# Heart_Rate_Monitoring_System.net
KiCad netlist of a schematic drawn in EAGLE
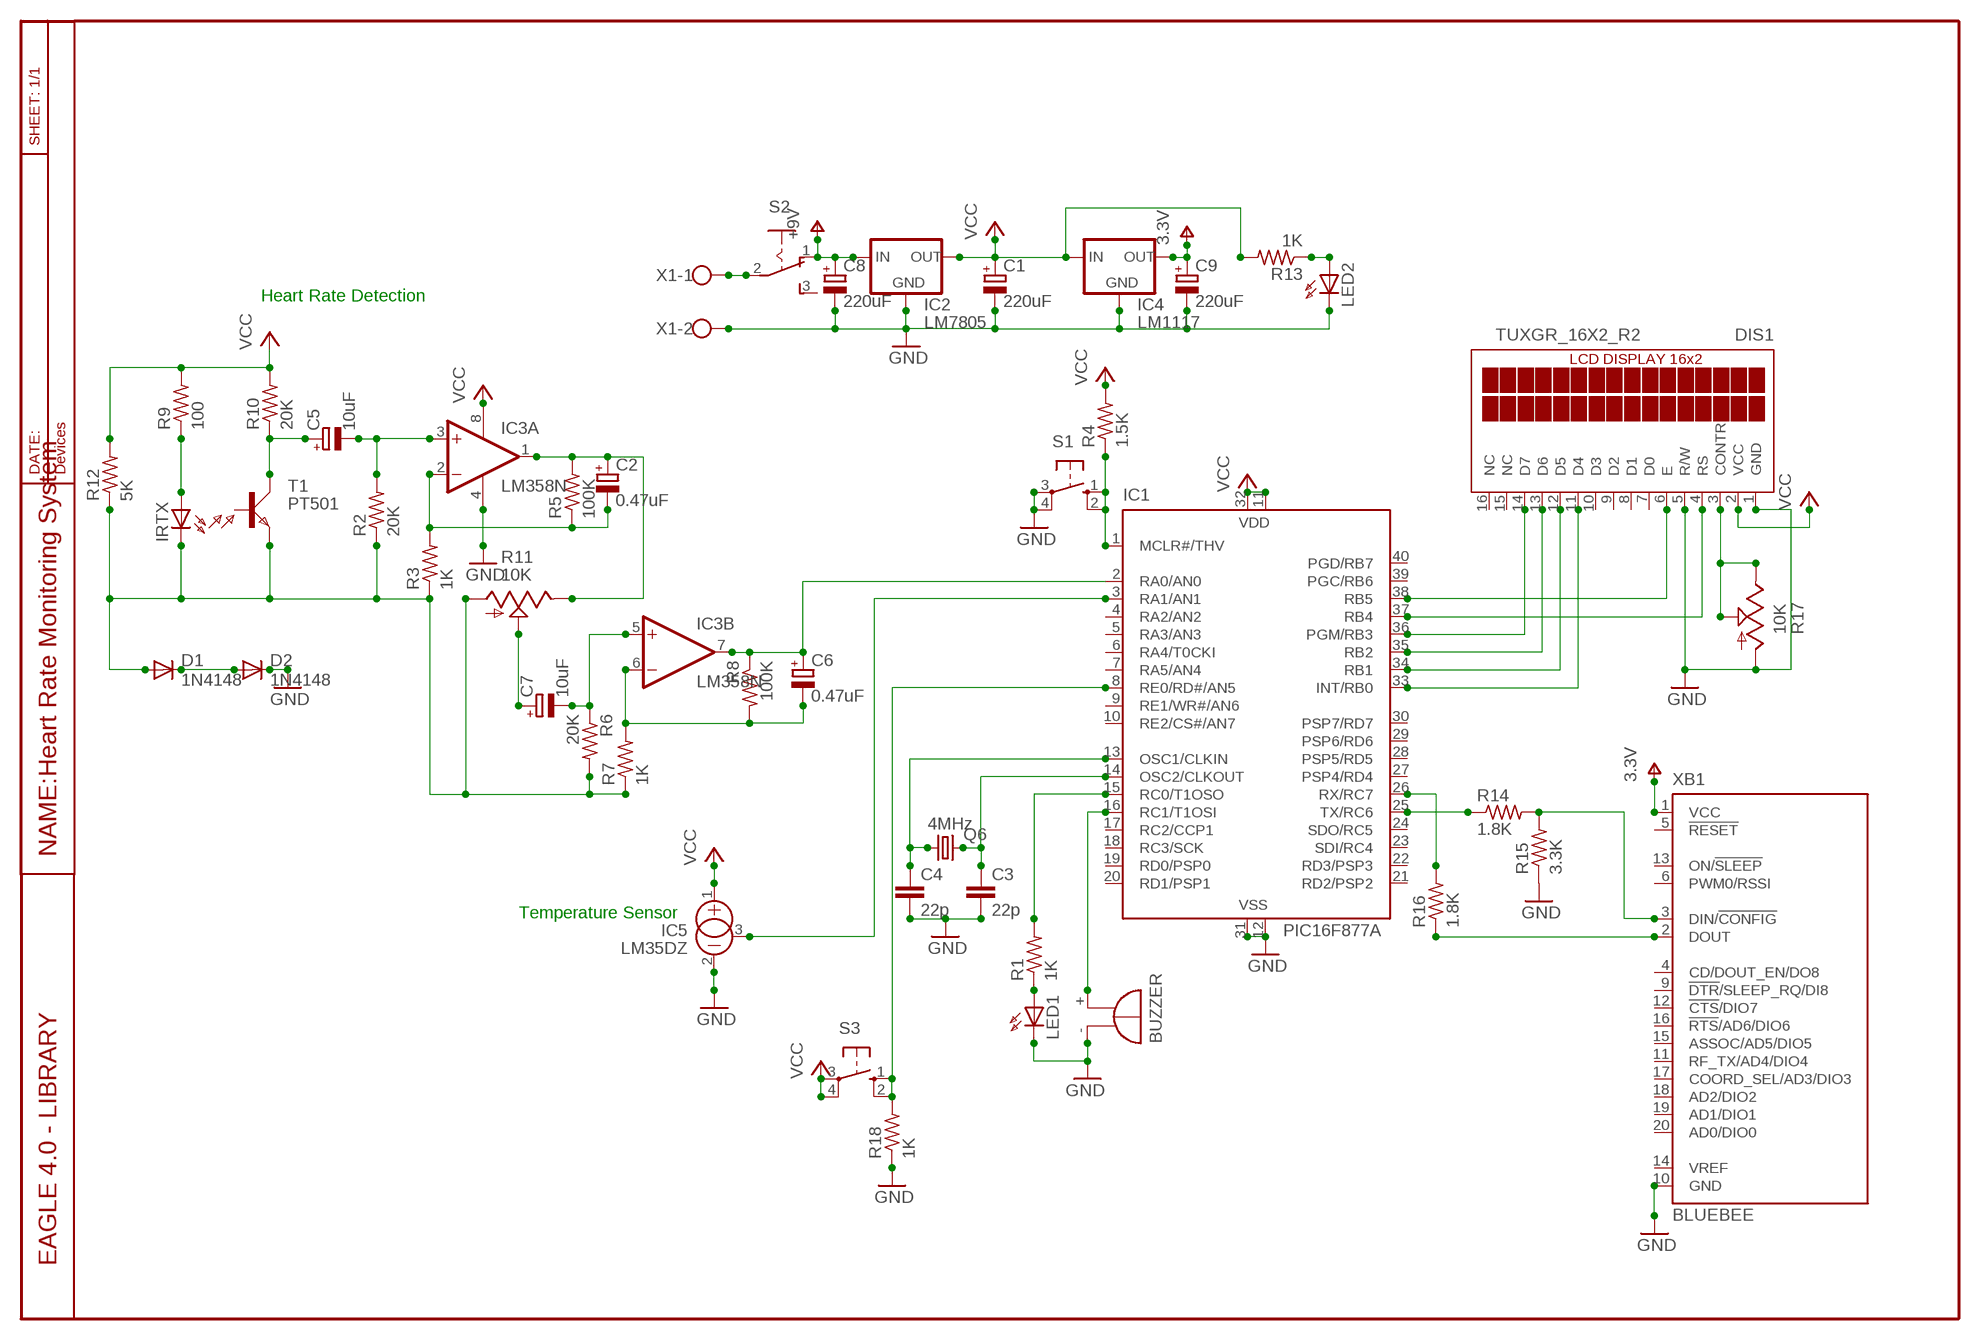
[diagram p0: schematic, sheet 1]

(export (version "E")
  (design (tool "Eeschema 10.0.6"))
  (components
    (comp (ref "BUZZER")
      (value "F/QMBIII")
      (footprint "eagle-import:F_QMBIII")
      (libsource (lib "eagle-import") (part "F/QMBIII"))
    )
    (comp (ref "C1")
      (value "220uF")
      (footprint "eagle-import:E3,5-10")
      (libsource (lib "eagle-import") (part "CPOL-EUE3.5-10"))
    )
    (comp (ref "C2")
      (value "0.47uF")
      (footprint "eagle-import:E2-5")
      (libsource (lib "eagle-import") (part "CPOL-EUE2-5"))
    )
    (comp (ref "C3")
      (value "22p")
      (footprint "eagle-import:C025-025X050")
      (libsource (lib "eagle-import") (part "C-EU025-025X050"))
    )
    (comp (ref "C4")
      (value "22p")
      (footprint "eagle-import:C025-025X050")
      (libsource (lib "eagle-import") (part "C-EU025-025X050"))
    )
    (comp (ref "C5")
      (value "10uF")
      (footprint "eagle-import:E2-5")
      (libsource (lib "eagle-import") (part "CPOL-EUE2-5"))
    )
    (comp (ref "C6")
      (value "0.47uF")
      (footprint "eagle-import:E2-5")
      (libsource (lib "eagle-import") (part "CPOL-EUE2-5"))
    )
    (comp (ref "C7")
      (value "10uF")
      (footprint "eagle-import:E2-5")
      (libsource (lib "eagle-import") (part "CPOL-EUE2-5"))
    )
    (comp (ref "C8")
      (value "220uF")
      (footprint "eagle-import:E3,5-10")
      (libsource (lib "eagle-import") (part "CPOL-EUE3.5-10"))
    )
    (comp (ref "C9")
      (value "220uF")
      (footprint "eagle-import:E3,5-10")
      (libsource (lib "eagle-import") (part "CPOL-EUE3.5-10"))
    )
    (comp (ref "D1")
      (value "1N4148")
      (footprint "eagle-import:DO35-7")
      (libsource (lib "eagle-import") (part "1N4148DO35-7"))
    )
    (comp (ref "D2")
      (value "1N4148")
      (footprint "eagle-import:DO35-7")
      (libsource (lib "eagle-import") (part "1N4148DO35-7"))
    )
    (comp (ref "DIS1")
      (value "TUXGR_16X2_R2")
      (footprint "eagle-import:TUXGR_16X2_R2")
      (libsource (lib "eagle-import") (part "TUXGR_16X2_R2"))
    )
    (comp (ref "IC1")
      (value "PIC16F877A")
      (footprint "eagle-import:DIL40")
      (libsource (lib "eagle-import") (part "PIC16F87P7"))
    )
    (comp (ref "IC2")
      (value "LM7805")
      (footprint "eagle-import:78MXXS")
      (libsource (lib "eagle-import") (part "78MXXS"))
    )
    (comp (ref "IC3")
      (value "LM358N")
      (footprint "eagle-import:DIL08")
      (libsource (lib "eagle-import") (part "LM358N"))
    )
    (comp (ref "IC4")
      (value "LM1117")
      (footprint "eagle-import:78MXXS")
      (libsource (lib "eagle-import") (part "78MXXS"))
    )
    (comp (ref "IC5")
      (value "LM35DZ")
      (footprint "eagle-import:TO92")
      (libsource (lib "eagle-import") (part "AD590ZR"))
    )
    (comp (ref "IRTX")
      (value "LED5MM")
      (footprint "eagle-import:LED5MM")
      (libsource (lib "eagle-import") (part "LED5MM"))
    )
    (comp (ref "LED1")
      (value "LED3MM")
      (footprint "eagle-import:LED3MM")
      (libsource (lib "eagle-import") (part "LED3MM"))
    )
    (comp (ref "LED2")
      (value "LED3MM")
      (footprint "eagle-import:LED3MM")
      (libsource (lib "eagle-import") (part "LED3MM"))
    )
    (comp (ref "Q6")
      (value "4MHz")
      (footprint "eagle-import:HC18U-V")
      (libsource (lib "eagle-import") (part "CRYTALHC18U-V"))
    )
    (comp (ref "R1")
      (value "1K")
      (footprint "eagle-import:0207_7")
      (libsource (lib "eagle-import") (part "R-US_0207/7"))
    )
    (comp (ref "R2")
      (value "20K")
      (footprint "eagle-import:0207_7")
      (libsource (lib "eagle-import") (part "R-US_0207/7"))
    )
    (comp (ref "R3")
      (value "1K")
      (footprint "eagle-import:0207_7")
      (libsource (lib "eagle-import") (part "R-US_0207/7"))
    )
    (comp (ref "R4")
      (value "1.5K")
      (footprint "eagle-import:0204_7")
      (libsource (lib "eagle-import") (part "R-US_0204/7"))
    )
    (comp (ref "R5")
      (value "100K")
      (footprint "eagle-import:0207_7")
      (libsource (lib "eagle-import") (part "R-US_0207/7"))
    )
    (comp (ref "R6")
      (value "20K")
      (footprint "eagle-import:0207_7")
      (libsource (lib "eagle-import") (part "R-US_0207/7"))
    )
    (comp (ref "R7")
      (value "1K")
      (footprint "eagle-import:0207_7")
      (libsource (lib "eagle-import") (part "R-US_0207/7"))
    )
    (comp (ref "R8")
      (value "100K")
      (footprint "eagle-import:0207_7")
      (libsource (lib "eagle-import") (part "R-US_0207/7"))
    )
    (comp (ref "R9")
      (value "100")
      (footprint "eagle-import:0207_7")
      (libsource (lib "eagle-import") (part "R-US_0207/7"))
    )
    (comp (ref "R10")
      (value "20K")
      (footprint "eagle-import:0207_7")
      (libsource (lib "eagle-import") (part "R-US_0207/7"))
    )
    (comp (ref "R11")
      (value "10K")
      (footprint "eagle-import:CA6V")
      (libsource (lib "eagle-import") (part "TRIM_US-CA6V"))
    )
    (comp (ref "R12")
      (value "5K")
      (footprint "eagle-import:0207_7")
      (libsource (lib "eagle-import") (part "R-US_0207/7"))
    )
    (comp (ref "R13")
      (value "1K")
      (footprint "eagle-import:0207_7")
      (libsource (lib "eagle-import") (part "R-US_0207/7"))
    )
    (comp (ref "R14")
      (value "1.8K")
      (footprint "eagle-import:0207_7")
      (libsource (lib "eagle-import") (part "R-US_0207/7"))
    )
    (comp (ref "R15")
      (value "3.3K")
      (footprint "eagle-import:0207_7")
      (libsource (lib "eagle-import") (part "R-US_0207/7"))
    )
    (comp (ref "R16")
      (value "1.8K")
      (footprint "eagle-import:0207_7")
      (libsource (lib "eagle-import") (part "R-US_0207/7"))
    )
    (comp (ref "R17")
      (value "10K")
      (footprint "eagle-import:CA6V")
      (libsource (lib "eagle-import") (part "TRIM_US-CA6V"))
    )
    (comp (ref "R18")
      (value "1K")
      (footprint "eagle-import:0207_7")
      (libsource (lib "eagle-import") (part "R-US_0207/7"))
    )
    (comp (ref "S1")
      (value "10-XX")
      (footprint "eagle-import:B3F-10XX")
      (libsource (lib "eagle-import") (part "10-XX"))
    )
    (comp (ref "S2")
      (value "255SB")
      (footprint "eagle-import:255SB")
      (libsource (lib "eagle-import") (part "255SB"))
    )
    (comp (ref "S3")
      (value "10-XX")
      (footprint "eagle-import:B3F-10XX")
      (libsource (lib "eagle-import") (part "10-XX"))
    )
    (comp (ref "T1")
      (value "PT501")
      (footprint "eagle-import:BP103")
      (libsource (lib "eagle-import") (part "BP103"))
    )
    (comp (ref "X1")
      (value "AK500/2")
      (footprint "eagle-import:AK500_2")
      (libsource (lib "eagle-import") (part "AK500/2"))
    )
    (comp (ref "XB1")
      (value "BLUEBEE")
      (footprint "eagle-import:XBEE")
      (fields (field (name "MPN") "XBP24-Z7UIT-004"))
      (libsource (lib "eagle-import") (part "XBEE"))
    )
  )
  (nets
    (net (code "1") (name "+9V") (class "Default")
      (node (ref "C8") (pin "+") (pinfunction "+_+") (pintype "passive"))
      (node (ref "C9") (pin "+") (pinfunction "+_+") (pintype "passive"))
      (node (ref "IC2") (pin "IN") (pinfunction "IN_IN") (pintype "input"))
      (node (ref "IC4") (pin "OUT") (pinfunction "OUT_OUT") (pintype "passive"))
      (node (ref "S2") (pin "1") (pinfunction "O_1") (pintype "passive"))
      (node (ref "XB1") (pin "1") (pinfunction "VCC_1") (pintype "power_in"))
    )
    (net (code "2") (name "GND") (class "Default")
      (node (ref "BUZZER") (pin "-") (pinfunction "+_-") (pintype "passive"))
      (node (ref "C1") (pin "-") (pinfunction "-_-") (pintype "passive"))
      (node (ref "C3") (pin "2") (pinfunction "2_2") (pintype "passive"))
      (node (ref "C4") (pin "2") (pinfunction "2_2") (pintype "passive"))
      (node (ref "C8") (pin "-") (pinfunction "-_-") (pintype "passive"))
      (node (ref "C9") (pin "-") (pinfunction "-_-") (pintype "passive"))
      (node (ref "D2") (pin "C") (pinfunction "C_C") (pintype "passive"))
      (node (ref "DIS1") (pin "1") (pinfunction "GND_1") (pintype "power_in"))
      (node (ref "DIS1") (pin "5") (pinfunction "R/W_5") (pintype "input"))
      (node (ref "IC1") (pin "12") (pinfunction "VSS_12") (pintype "power_in"))
      (node (ref "IC1") (pin "31") (pinfunction "VSS_31") (pintype "power_in"))
      (node (ref "IC2") (pin "GND") (pinfunction "GND_GND") (pintype "input"))
      (node (ref "IC3") (pin "4") (pinfunction "V-_4") (pintype "power_in"))
      (node (ref "IC4") (pin "GND") (pinfunction "GND_GND") (pintype "input"))
      (node (ref "IC5") (pin "2") (pinfunction "-_2") (pintype "input"))
      (node (ref "LED1") (pin "K") (pinfunction "C_K") (pintype "passive"))
      (node (ref "LED2") (pin "K") (pinfunction "C_K") (pintype "passive"))
      (node (ref "R15") (pin "1") (pinfunction "1_1") (pintype "passive"))
      (node (ref "R17") (pin "A") (pinfunction "A_A") (pintype "passive"))
      (node (ref "R18") (pin "1") (pinfunction "1_1") (pintype "passive"))
      (node (ref "S1") (pin "3") (pinfunction "P_3") (pintype "passive"))
      (node (ref "S1") (pin "4") (pinfunction "P1_4") (pintype "passive"))
      (node (ref "X1") (pin "2") (pinfunction "KL_2") (pintype "passive"))
      (node (ref "XB1") (pin "10") (pinfunction "GND_10") (pintype "power_in"))
    )
    (net (code "3") (name "Net-(BUZZER--)") (class "Default")
      (node (ref "BUZZER") (pin "+") (pinfunction "-_+") (pintype "passive"))
      (node (ref "IC1") (pin "16") (pinfunction "RC1/T1OSI_16") (pintype "bidirectional"))
    )
    (net (code "4") (name "Net-(C5-Pad+)") (class "Default")
      (node (ref "C5") (pin "+") (pinfunction "+_+") (pintype "passive"))
      (node (ref "R10") (pin "1") (pinfunction "1_1") (pintype "passive"))
      (node (ref "T1") (pin "C") (pinfunction "C_C") (pintype "passive"))
    )
    (net (code "5") (name "Net-(C7-Pad+)") (class "Default")
      (node (ref "C7") (pin "+") (pinfunction "+_+") (pintype "passive"))
      (node (ref "R11") (pin "S") (pinfunction "S_S") (pintype "passive"))
    )
    (net (code "6") (name "Net-(D1-PadC)") (class "Default")
      (node (ref "D1") (pin "C") (pinfunction "C_C") (pintype "passive"))
      (node (ref "D2") (pin "A") (pinfunction "A_A") (pintype "passive"))
    )
    (net (code "7") (name "Net-(DIS1-CONTR)") (class "Default")
      (node (ref "DIS1") (pin "3") (pinfunction "CONTR_3") (pintype "input"))
      (node (ref "R17") (pin "E") (pinfunction "E_E") (pintype "passive"))
      (node (ref "R17") (pin "S") (pinfunction "S_S") (pintype "passive"))
    )
    (net (code "8") (name "Net-(DIS1-D4)") (class "Default")
      (node (ref "DIS1") (pin "11") (pinfunction "D4_11") (pintype "input"))
      (node (ref "IC1") (pin "33") (pinfunction "INT/RB0_33") (pintype "bidirectional"))
    )
    (net (code "9") (name "Net-(DIS1-D5)") (class "Default")
      (node (ref "DIS1") (pin "12") (pinfunction "D5_12") (pintype "input"))
      (node (ref "IC1") (pin "34") (pinfunction "RB1_34") (pintype "bidirectional"))
    )
    (net (code "10") (name "Net-(DIS1-D6)") (class "Default")
      (node (ref "DIS1") (pin "13") (pinfunction "D6_13") (pintype "input"))
      (node (ref "IC1") (pin "35") (pinfunction "RB2_35") (pintype "bidirectional"))
    )
    (net (code "11") (name "Net-(DIS1-D7)") (class "Default")
      (node (ref "DIS1") (pin "14") (pinfunction "D7_14") (pintype "input"))
      (node (ref "IC1") (pin "36") (pinfunction "PGM/RB3_36") (pintype "bidirectional"))
    )
    (net (code "12") (name "Net-(DIS1-E)") (class "Default")
      (node (ref "DIS1") (pin "6") (pinfunction "E_6") (pintype "input"))
      (node (ref "IC1") (pin "38") (pinfunction "RB5_38") (pintype "bidirectional"))
    )
    (net (code "13") (name "Net-(DIS1-RS)") (class "Default")
      (node (ref "DIS1") (pin "4") (pinfunction "RS_4") (pintype "input"))
      (node (ref "IC1") (pin "37") (pinfunction "RB4_37") (pintype "bidirectional"))
    )
    (net (code "14") (name "Net-(IC1-MCLR#{slash}THV)") (class "Default")
      (node (ref "IC1") (pin "1") (pinfunction "MCLR#/THV_1") (pintype "input"))
      (node (ref "R4") (pin "1") (pinfunction "1_1") (pintype "passive"))
      (node (ref "S1") (pin "1") (pinfunction "S_1") (pintype "passive"))
      (node (ref "S1") (pin "2") (pinfunction "S1_2") (pintype "passive"))
    )
    (net (code "15") (name "Net-(IC1-OSC1{slash}CLKIN)") (class "Default")
      (node (ref "C4") (pin "1") (pinfunction "1_1") (pintype "passive"))
      (node (ref "IC1") (pin "13") (pinfunction "OSC1/CLKIN_13") (pintype "input"))
      (node (ref "Q6") (pin "1") (pinfunction "1_1") (pintype "passive"))
    )
    (net (code "16") (name "Net-(IC1-OSC2{slash}CLKOUT)") (class "Default")
      (node (ref "C3") (pin "1") (pinfunction "1_1") (pintype "passive"))
      (node (ref "IC1") (pin "14") (pinfunction "OSC2/CLKOUT_14") (pintype "output"))
      (node (ref "Q6") (pin "2") (pinfunction "2_2") (pintype "passive"))
    )
    (net (code "17") (name "Net-(IC1-RA0{slash}AN0)") (class "Default")
      (node (ref "C6") (pin "+") (pinfunction "+_+") (pintype "passive"))
      (node (ref "IC1") (pin "2") (pinfunction "RA0/AN0_2") (pintype "bidirectional"))
      (node (ref "IC3") (pin "7") (pinfunction "OUT_7") (pintype "output"))
      (node (ref "R8") (pin "1") (pinfunction "1_1") (pintype "passive"))
    )
    (net (code "18") (name "Net-(IC1-RA1{slash}AN1)") (class "Default")
      (node (ref "IC1") (pin "3") (pinfunction "RA1/AN1_3") (pintype "bidirectional"))
      (node (ref "IC5") (pin "3") (pinfunction "CAN_3") (pintype "passive"))
    )
    (net (code "19") (name "Net-(IC1-RC0{slash}T1OSO)") (class "Default")
      (node (ref "IC1") (pin "15") (pinfunction "RC0/T1OSO_15") (pintype "bidirectional"))
      (node (ref "R1") (pin "2") (pinfunction "2_2") (pintype "passive"))
    )
    (net (code "20") (name "Net-(IC1-RE0{slash}RD#{slash}AN5)") (class "Default")
      (node (ref "IC1") (pin "8") (pinfunction "RE0/RD#/AN5_8") (pintype "bidirectional"))
      (node (ref "R18") (pin "2") (pinfunction "2_2") (pintype "passive"))
      (node (ref "S3") (pin "1") (pinfunction "S_1") (pintype "passive"))
      (node (ref "S3") (pin "2") (pinfunction "S1_2") (pintype "passive"))
    )
    (net (code "21") (name "Net-(IC1-RX{slash}RC7)") (class "Default")
      (node (ref "IC1") (pin "26") (pinfunction "RX/RC7_26") (pintype "bidirectional"))
      (node (ref "R16") (pin "2") (pinfunction "2_2") (pintype "passive"))
    )
    (net (code "22") (name "Net-(IC1-TX{slash}RC6)") (class "Default")
      (node (ref "IC1") (pin "25") (pinfunction "TX/RC6_25") (pintype "bidirectional"))
      (node (ref "R14") (pin "1") (pinfunction "1_1") (pintype "passive"))
    )
    (net (code "23") (name "Net-(IC3A-+IN)") (class "Default")
      (node (ref "C5") (pin "-") (pinfunction "-_-") (pintype "passive"))
      (node (ref "IC3") (pin "3") (pinfunction "+IN_3") (pintype "input"))
      (node (ref "R2") (pin "2") (pinfunction "2_2") (pintype "passive"))
    )
    (net (code "24") (name "Net-(IC3A--IN)") (class "Default")
      (node (ref "C2") (pin "-") (pinfunction "-_-") (pintype "passive"))
      (node (ref "IC3") (pin "2") (pinfunction "-IN_2") (pintype "input"))
      (node (ref "R3") (pin "2") (pinfunction "2_2") (pintype "passive"))
      (node (ref "R5") (pin "1") (pinfunction "1_1") (pintype "passive"))
    )
    (net (code "25") (name "Net-(IC3A-OUT)") (class "Default")
      (node (ref "C2") (pin "+") (pinfunction "+_+") (pintype "passive"))
      (node (ref "IC3") (pin "1") (pinfunction "OUT_1") (pintype "output"))
      (node (ref "R11") (pin "E") (pinfunction "E_E") (pintype "passive"))
      (node (ref "R5") (pin "2") (pinfunction "2_2") (pintype "passive"))
    )
    (net (code "26") (name "Net-(IC3B-+IN)") (class "Default")
      (node (ref "C7") (pin "-") (pinfunction "-_-") (pintype "passive"))
      (node (ref "IC3") (pin "5") (pinfunction "+IN_5") (pintype "input"))
      (node (ref "R6") (pin "1") (pinfunction "1_1") (pintype "passive"))
    )
    (net (code "27") (name "Net-(IC3B--IN)") (class "Default")
      (node (ref "C6") (pin "-") (pinfunction "-_-") (pintype "passive"))
      (node (ref "IC3") (pin "6") (pinfunction "-IN_6") (pintype "input"))
      (node (ref "R7") (pin "2") (pinfunction "2_2") (pintype "passive"))
      (node (ref "R8") (pin "2") (pinfunction "2_2") (pintype "passive"))
    )
    (net (code "28") (name "Net-(IRTX-C)") (class "Default")
      (node (ref "D1") (pin "A") (pinfunction "A_A") (pintype "passive"))
      (node (ref "IRTX") (pin "K") (pinfunction "C_K") (pintype "passive"))
      (node (ref "R11") (pin "A") (pinfunction "A_A") (pintype "passive"))
      (node (ref "R12") (pin "1") (pinfunction "1_1") (pintype "passive"))
      (node (ref "R2") (pin "1") (pinfunction "1_1") (pintype "passive"))
      (node (ref "R3") (pin "1") (pinfunction "1_1") (pintype "passive"))
      (node (ref "R6") (pin "2") (pinfunction "2_2") (pintype "passive"))
      (node (ref "R7") (pin "1") (pinfunction "1_1") (pintype "passive"))
      (node (ref "T1") (pin "E") (pinfunction "E_E") (pintype "passive"))
    )
    (net (code "29") (name "Net-(IRTX-PadA)") (class "Default")
      (node (ref "IRTX") (pin "A") (pinfunction "A_A") (pintype "passive"))
      (node (ref "R9") (pin "1") (pinfunction "1_1") (pintype "passive"))
    )
    (net (code "30") (name "Net-(LED1-PadA)") (class "Default")
      (node (ref "LED1") (pin "A") (pinfunction "A_A") (pintype "passive"))
      (node (ref "R1") (pin "1") (pinfunction "1_1") (pintype "passive"))
    )
    (net (code "31") (name "Net-(LED2-PadA)") (class "Default")
      (node (ref "LED2") (pin "A") (pinfunction "A_A") (pintype "passive"))
      (node (ref "R13") (pin "1") (pinfunction "1_1") (pintype "passive"))
    )
    (net (code "32") (name "Net-(S2-P)") (class "Default")
      (node (ref "S2") (pin "2") (pinfunction "P_2") (pintype "passive"))
      (node (ref "X1") (pin "1") (pinfunction "KL_1") (pintype "passive"))
    )
    (net (code "33") (name "Net-(XB1-DIN{slash}~{CONFIG})") (class "Default")
      (node (ref "R14") (pin "2") (pinfunction "2_2") (pintype "passive"))
      (node (ref "R15") (pin "2") (pinfunction "2_2") (pintype "passive"))
      (node (ref "XB1") (pin "3") (pinfunction "DIN/~{CONFIG}_3") (pintype "input"))
    )
    (net (code "34") (name "Net-(XB1-DOUT)") (class "Default")
      (node (ref "R16") (pin "1") (pinfunction "1_1") (pintype "passive"))
      (node (ref "XB1") (pin "2") (pinfunction "DOUT_2") (pintype "output"))
    )
    (net (code "35") (name "VCC") (class "Default")
      (node (ref "C1") (pin "+") (pinfunction "+_+") (pintype "passive"))
      (node (ref "DIS1") (pin "2") (pinfunction "VCC_2") (pintype "power_in"))
      (node (ref "IC1") (pin "11") (pinfunction "VDD_11") (pintype "power_in"))
      (node (ref "IC1") (pin "32") (pinfunction "VDD_32") (pintype "power_in"))
      (node (ref "IC2") (pin "OUT") (pinfunction "OUT_OUT") (pintype "passive"))
      (node (ref "IC3") (pin "8") (pinfunction "V+_8") (pintype "power_in"))
      (node (ref "IC4") (pin "IN") (pinfunction "IN_IN") (pintype "input"))
      (node (ref "IC5") (pin "1") (pinfunction "+_1") (pintype "input"))
      (node (ref "R10") (pin "2") (pinfunction "2_2") (pintype "passive"))
      (node (ref "R12") (pin "2") (pinfunction "2_2") (pintype "passive"))
      (node (ref "R13") (pin "2") (pinfunction "2_2") (pintype "passive"))
      (node (ref "R4") (pin "2") (pinfunction "2_2") (pintype "passive"))
      (node (ref "R9") (pin "2") (pinfunction "2_2") (pintype "passive"))
      (node (ref "S3") (pin "3") (pinfunction "P_3") (pintype "passive"))
      (node (ref "S3") (pin "4") (pinfunction "P1_4") (pintype "passive"))
    )
    (net (code "36") (name "unconnected-(DIS1-D0-Pad7)") (class "Default")
      (node (ref "DIS1") (pin "7") (pinfunction "D0_7") (pintype "input"))
    )
    (net (code "37") (name "unconnected-(DIS1-D1-Pad8)") (class "Default")
      (node (ref "DIS1") (pin "8") (pinfunction "D1_8") (pintype "input"))
    )
    (net (code "38") (name "unconnected-(DIS1-D2-Pad9)") (class "Default")
      (node (ref "DIS1") (pin "9") (pinfunction "D2_9") (pintype "input"))
    )
    (net (code "39") (name "unconnected-(DIS1-D3-Pad10)") (class "Default")
      (node (ref "DIS1") (pin "10") (pinfunction "D3_10") (pintype "input"))
    )
    (net (code "40") (name "unconnected-(DIS1-NC-Pad15)") (class "Default")
      (node (ref "DIS1") (pin "15") (pinfunction "NC_15") (pintype "no_connect"))
    )
    (net (code "41") (name "unconnected-(DIS1-NC-Pad16)") (class "Default")
      (node (ref "DIS1") (pin "16") (pinfunction "NC_16") (pintype "no_connect"))
    )
    (net (code "42") (name "unconnected-(IC1-PGC{slash}RB6-Pad39)") (class "Default")
      (node (ref "IC1") (pin "39") (pinfunction "PGC/RB6_39") (pintype "bidirectional"))
    )
    (net (code "43") (name "unconnected-(IC1-PGD{slash}RB7-Pad40)") (class "Default")
      (node (ref "IC1") (pin "40") (pinfunction "PGD/RB7_40") (pintype "bidirectional"))
    )
    (net (code "44") (name "unconnected-(IC1-PSP4{slash}RD4-Pad27)") (class "Default")
      (node (ref "IC1") (pin "27") (pinfunction "PSP4/RD4_27") (pintype "bidirectional"))
    )
    (net (code "45") (name "unconnected-(IC1-PSP5{slash}RD5-Pad28)") (class "Default")
      (node (ref "IC1") (pin "28") (pinfunction "PSP5/RD5_28") (pintype "bidirectional"))
    )
    (net (code "46") (name "unconnected-(IC1-PSP6{slash}RD6-Pad29)") (class "Default")
      (node (ref "IC1") (pin "29") (pinfunction "PSP6/RD6_29") (pintype "bidirectional"))
    )
    (net (code "47") (name "unconnected-(IC1-PSP7{slash}RD7-Pad30)") (class "Default")
      (node (ref "IC1") (pin "30") (pinfunction "PSP7/RD7_30") (pintype "bidirectional"))
    )
    (net (code "48") (name "unconnected-(IC1-RA2{slash}AN2-Pad4)") (class "Default")
      (node (ref "IC1") (pin "4") (pinfunction "RA2/AN2_4") (pintype "bidirectional"))
    )
    (net (code "49") (name "unconnected-(IC1-RA3{slash}AN3-Pad5)") (class "Default")
      (node (ref "IC1") (pin "5") (pinfunction "RA3/AN3_5") (pintype "bidirectional"))
    )
    (net (code "50") (name "unconnected-(IC1-RA4{slash}T0CKI-Pad6)") (class "Default")
      (node (ref "IC1") (pin "6") (pinfunction "RA4/T0CKI_6") (pintype "bidirectional"))
    )
    (net (code "51") (name "unconnected-(IC1-RA5{slash}AN4-Pad7)") (class "Default")
      (node (ref "IC1") (pin "7") (pinfunction "RA5/AN4_7") (pintype "bidirectional"))
    )
    (net (code "52") (name "unconnected-(IC1-RC2{slash}CCP1-Pad17)") (class "Default")
      (node (ref "IC1") (pin "17") (pinfunction "RC2/CCP1_17") (pintype "bidirectional"))
    )
    (net (code "53") (name "unconnected-(IC1-RC3{slash}SCK-Pad18)") (class "Default")
      (node (ref "IC1") (pin "18") (pinfunction "RC3/SCK_18") (pintype "bidirectional"))
    )
    (net (code "54") (name "unconnected-(IC1-RD0{slash}PSP0-Pad19)") (class "Default")
      (node (ref "IC1") (pin "19") (pinfunction "RD0/PSP0_19") (pintype "bidirectional"))
    )
    (net (code "55") (name "unconnected-(IC1-RD1{slash}PSP1-Pad20)") (class "Default")
      (node (ref "IC1") (pin "20") (pinfunction "RD1/PSP1_20") (pintype "bidirectional"))
    )
    (net (code "56") (name "unconnected-(IC1-RD2{slash}PSP2-Pad21)") (class "Default")
      (node (ref "IC1") (pin "21") (pinfunction "RD2/PSP2_21") (pintype "bidirectional"))
    )
    (net (code "57") (name "unconnected-(IC1-RD3{slash}PSP3-Pad22)") (class "Default")
      (node (ref "IC1") (pin "22") (pinfunction "RD3/PSP3_22") (pintype "bidirectional"))
    )
    (net (code "58") (name "unconnected-(IC1-RE1{slash}WR#{slash}AN6-Pad9)") (class "Default")
      (node (ref "IC1") (pin "9") (pinfunction "RE1/WR#/AN6_9") (pintype "bidirectional"))
    )
    (net (code "59") (name "unconnected-(IC1-RE2{slash}CS#{slash}AN7-Pad10)") (class "Default")
      (node (ref "IC1") (pin "10") (pinfunction "RE2/CS#/AN7_10") (pintype "bidirectional"))
    )
    (net (code "60") (name "unconnected-(IC1-SDI{slash}RC4-Pad23)") (class "Default")
      (node (ref "IC1") (pin "23") (pinfunction "SDI/RC4_23") (pintype "bidirectional"))
    )
    (net (code "61") (name "unconnected-(IC1-SDO{slash}RC5-Pad24)") (class "Default")
      (node (ref "IC1") (pin "24") (pinfunction "SDO/RC5_24") (pintype "bidirectional"))
    )
    (net (code "62") (name "unconnected-(S2-S-Pad3)") (class "Default")
      (node (ref "S2") (pin "3") (pinfunction "S_3") (pintype "passive"))
    )
    (net (code "63") (name "unconnected-(T1-PadB)") (class "Default")
      (node (ref "T1") (pin "B") (pinfunction "B_B") (pintype "passive"))
    )
    (net (code "64") (name "unconnected-(XB1-AD0{slash}DIO0-Pad20)") (class "Default")
      (node (ref "XB1") (pin "20") (pinfunction "AD0/DIO0_20") (pintype "bidirectional"))
    )
    (net (code "65") (name "unconnected-(XB1-AD1{slash}DIO1-Pad19)") (class "Default")
      (node (ref "XB1") (pin "19") (pinfunction "AD1/DIO1_19") (pintype "bidirectional"))
    )
    (net (code "66") (name "unconnected-(XB1-AD2{slash}DIO2-Pad18)") (class "Default")
      (node (ref "XB1") (pin "18") (pinfunction "AD2/DIO2_18") (pintype "bidirectional"))
    )
    (net (code "67") (name "unconnected-(XB1-ASSOC{slash}AD5{slash}DIO5-Pad15)") (class "Default")
      (node (ref "XB1") (pin "15") (pinfunction "ASSOC/AD5/DIO5_15") (pintype "bidirectional"))
    )
    (net (code "68") (name "unconnected-(XB1-CD{slash}DOUT_EN{slash}DO8-Pad4)") (class "Default")
      (node (ref "XB1") (pin "4") (pinfunction "CD/DOUT_EN/DO8_4") (pintype "output"))
    )
    (net (code "69") (name "unconnected-(XB1-COORD_SEL{slash}AD3{slash}DIO3-Pad17)") (class "Default")
      (node (ref "XB1") (pin "17") (pinfunction "COORD_SEL/AD3/DIO3_17") (pintype "bidirectional"))
    )
    (net (code "70") (name "unconnected-(XB1-ON{slash}~{SLEEP}-Pad13)") (class "Default")
      (node (ref "XB1") (pin "13") (pinfunction "ON/~{SLEEP}_13") (pintype "output"))
    )
    (net (code "71") (name "unconnected-(XB1-PWM0{slash}RSSI-Pad6)") (class "Default")
      (node (ref "XB1") (pin "6") (pinfunction "PWM0/RSSI_6") (pintype "output"))
    )
    (net (code "72") (name "unconnected-(XB1-RF_TX{slash}AD4{slash}DIO4-Pad11)") (class "Default")
      (node (ref "XB1") (pin "11") (pinfunction "RF_TX/AD4/DIO4_11") (pintype "bidirectional"))
    )
    (net (code "73") (name "unconnected-(XB1-VREF-Pad14)") (class "Default")
      (node (ref "XB1") (pin "14") (pinfunction "VREF_14") (pintype "input"))
    )
    (net (code "74") (name "unconnected-(XB1-~{CTS}{slash}DIO7-Pad12)") (class "Default")
      (node (ref "XB1") (pin "12") (pinfunction "~{CTS}/DIO7_12") (pintype "bidirectional"))
    )
    (net (code "75") (name "unconnected-(XB1-~{DTR}{slash}SLEEP_RQ{slash}DI8-Pad9)") (class "Default")
      (node (ref "XB1") (pin "9") (pinfunction "~{DTR}/SLEEP_RQ/DI8_9") (pintype "bidirectional"))
    )
    (net (code "76") (name "unconnected-(XB1-~{RESET}-Pad5)") (class "Default")
      (node (ref "XB1") (pin "5") (pinfunction "~{RESET}_5") (pintype "input"))
    )
    (net (code "77") (name "unconnected-(XB1-~{RTS}{slash}AD6{slash}DIO6-Pad16)") (class "Default")
      (node (ref "XB1") (pin "16") (pinfunction "~{RTS}/AD6/DIO6_16") (pintype "bidirectional"))
    )
  )
)
